# 4x4.net
KiCad netlist of a schematic drawn in EasyEDA Pro
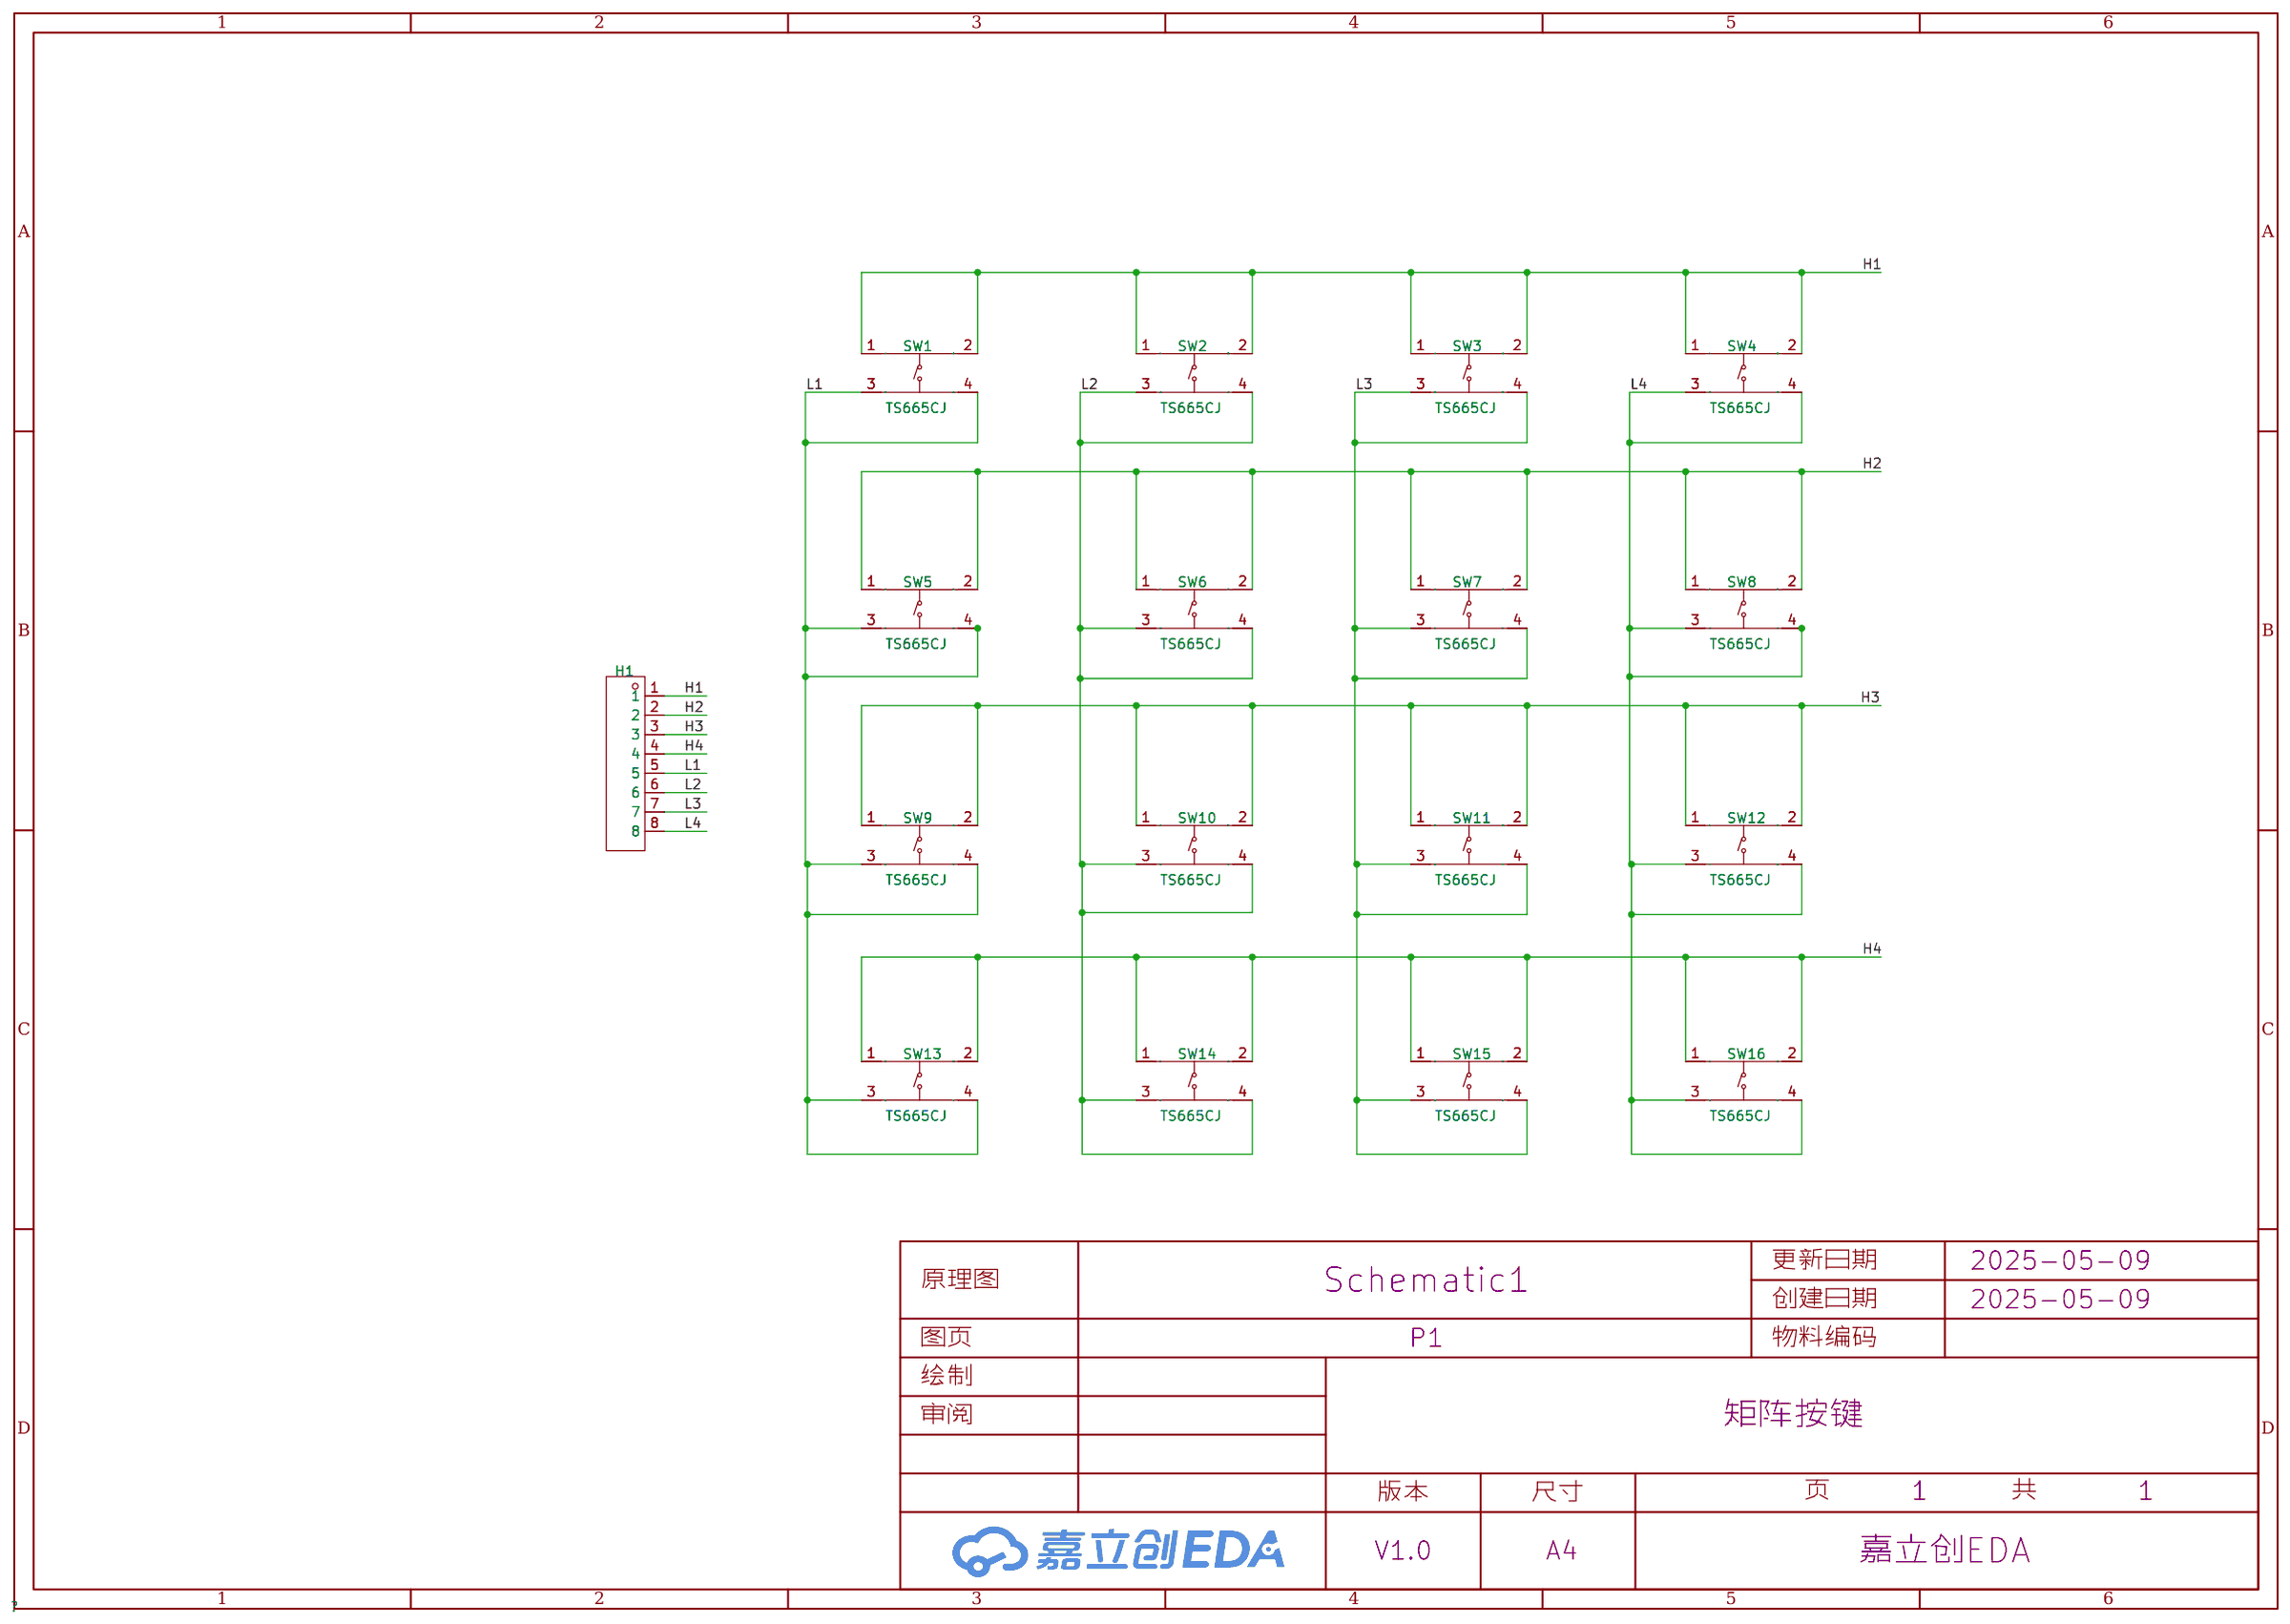
[diagram p0: schematic sheet]

(export (version "E")
  (design (tool "Eeschema 10.0.6"))
  (components
    (comp (ref "H1")
      (value "PZ254V-11-08P")
      (footprint "easyedapro:HDR-TH_8P-P2.54-V-M")
      (fields (field (name "Manufacturer") "XFCN(兴飞)"))
      (libsource (lib "easyedapro") (part "PZ254V-11-08P"))
    )
    (comp (ref "SW1")
      (value "TS665CJ")
      (footprint "easyedapro:SW-TH_4P-L6.0-W6.0-P4.50-LS6.5")
      (description "电路结构:单刀单掷;按钮形状:圆形按钮;安装方式:直插;开关长度:6mm;开关宽度:6mm;开关高度:5mm;触点电流:50mA;额定电压(DC):12V;带灯:-;机械寿命:-;")
      (fields (field (name "Manufacturer") "SHOU HAN(首韩)"))
      (libsource (lib "easyedapro") (part "TS665CJ"))
    )
    (comp (ref "SW2")
      (value "TS665CJ")
      (footprint "easyedapro:SW-TH_4P-L6.0-W6.0-P4.50-LS6.5")
      (description "电路结构:单刀单掷;按钮形状:圆形按钮;安装方式:直插;开关长度:6mm;开关宽度:6mm;开关高度:5mm;触点电流:50mA;额定电压(DC):12V;带灯:-;机械寿命:-;")
      (fields (field (name "Manufacturer") "SHOU HAN(首韩)"))
      (libsource (lib "easyedapro") (part "TS665CJ"))
    )
    (comp (ref "SW3")
      (value "TS665CJ")
      (footprint "easyedapro:SW-TH_4P-L6.0-W6.0-P4.50-LS6.5")
      (description "电路结构:单刀单掷;按钮形状:圆形按钮;安装方式:直插;开关长度:6mm;开关宽度:6mm;开关高度:5mm;触点电流:50mA;额定电压(DC):12V;带灯:-;机械寿命:-;")
      (fields (field (name "Manufacturer") "SHOU HAN(首韩)"))
      (libsource (lib "easyedapro") (part "TS665CJ"))
    )
    (comp (ref "SW4")
      (value "TS665CJ")
      (footprint "easyedapro:SW-TH_4P-L6.0-W6.0-P4.50-LS6.5")
      (description "电路结构:单刀单掷;按钮形状:圆形按钮;安装方式:直插;开关长度:6mm;开关宽度:6mm;开关高度:5mm;触点电流:50mA;额定电压(DC):12V;带灯:-;机械寿命:-;")
      (fields (field (name "Manufacturer") "SHOU HAN(首韩)"))
      (libsource (lib "easyedapro") (part "TS665CJ"))
    )
    (comp (ref "SW5")
      (value "TS665CJ")
      (footprint "easyedapro:SW-TH_4P-L6.0-W6.0-P4.50-LS6.5")
      (description "电路结构:单刀单掷;按钮形状:圆形按钮;安装方式:直插;开关长度:6mm;开关宽度:6mm;开关高度:5mm;触点电流:50mA;额定电压(DC):12V;带灯:-;机械寿命:-;")
      (fields (field (name "Manufacturer") "SHOU HAN(首韩)"))
      (libsource (lib "easyedapro") (part "TS665CJ"))
    )
    (comp (ref "SW6")
      (value "TS665CJ")
      (footprint "easyedapro:SW-TH_4P-L6.0-W6.0-P4.50-LS6.5")
      (description "电路结构:单刀单掷;按钮形状:圆形按钮;安装方式:直插;开关长度:6mm;开关宽度:6mm;开关高度:5mm;触点电流:50mA;额定电压(DC):12V;带灯:-;机械寿命:-;")
      (fields (field (name "Manufacturer") "SHOU HAN(首韩)"))
      (libsource (lib "easyedapro") (part "TS665CJ"))
    )
    (comp (ref "SW7")
      (value "TS665CJ")
      (footprint "easyedapro:SW-TH_4P-L6.0-W6.0-P4.50-LS6.5")
      (description "电路结构:单刀单掷;按钮形状:圆形按钮;安装方式:直插;开关长度:6mm;开关宽度:6mm;开关高度:5mm;触点电流:50mA;额定电压(DC):12V;带灯:-;机械寿命:-;")
      (fields (field (name "Manufacturer") "SHOU HAN(首韩)"))
      (libsource (lib "easyedapro") (part "TS665CJ"))
    )
    (comp (ref "SW8")
      (value "TS665CJ")
      (footprint "easyedapro:SW-TH_4P-L6.0-W6.0-P4.50-LS6.5")
      (description "电路结构:单刀单掷;按钮形状:圆形按钮;安装方式:直插;开关长度:6mm;开关宽度:6mm;开关高度:5mm;触点电流:50mA;额定电压(DC):12V;带灯:-;机械寿命:-;")
      (fields (field (name "Manufacturer") "SHOU HAN(首韩)"))
      (libsource (lib "easyedapro") (part "TS665CJ"))
    )
    (comp (ref "SW9")
      (value "TS665CJ")
      (footprint "easyedapro:SW-TH_4P-L6.0-W6.0-P4.50-LS6.5")
      (description "电路结构:单刀单掷;按钮形状:圆形按钮;安装方式:直插;开关长度:6mm;开关宽度:6mm;开关高度:5mm;触点电流:50mA;额定电压(DC):12V;带灯:-;机械寿命:-;")
      (fields (field (name "Manufacturer") "SHOU HAN(首韩)"))
      (libsource (lib "easyedapro") (part "TS665CJ"))
    )
    (comp (ref "SW10")
      (value "TS665CJ")
      (footprint "easyedapro:SW-TH_4P-L6.0-W6.0-P4.50-LS6.5")
      (description "电路结构:单刀单掷;按钮形状:圆形按钮;安装方式:直插;开关长度:6mm;开关宽度:6mm;开关高度:5mm;触点电流:50mA;额定电压(DC):12V;带灯:-;机械寿命:-;")
      (fields (field (name "Manufacturer") "SHOU HAN(首韩)"))
      (libsource (lib "easyedapro") (part "TS665CJ"))
    )
    (comp (ref "SW11")
      (value "TS665CJ")
      (footprint "easyedapro:SW-TH_4P-L6.0-W6.0-P4.50-LS6.5")
      (description "电路结构:单刀单掷;按钮形状:圆形按钮;安装方式:直插;开关长度:6mm;开关宽度:6mm;开关高度:5mm;触点电流:50mA;额定电压(DC):12V;带灯:-;机械寿命:-;")
      (fields (field (name "Manufacturer") "SHOU HAN(首韩)"))
      (libsource (lib "easyedapro") (part "TS665CJ"))
    )
    (comp (ref "SW12")
      (value "TS665CJ")
      (footprint "easyedapro:SW-TH_4P-L6.0-W6.0-P4.50-LS6.5")
      (description "电路结构:单刀单掷;按钮形状:圆形按钮;安装方式:直插;开关长度:6mm;开关宽度:6mm;开关高度:5mm;触点电流:50mA;额定电压(DC):12V;带灯:-;机械寿命:-;")
      (fields (field (name "Manufacturer") "SHOU HAN(首韩)"))
      (libsource (lib "easyedapro") (part "TS665CJ"))
    )
    (comp (ref "SW13")
      (value "TS665CJ")
      (footprint "easyedapro:SW-TH_4P-L6.0-W6.0-P4.50-LS6.5")
      (description "电路结构:单刀单掷;按钮形状:圆形按钮;安装方式:直插;开关长度:6mm;开关宽度:6mm;开关高度:5mm;触点电流:50mA;额定电压(DC):12V;带灯:-;机械寿命:-;")
      (fields (field (name "Manufacturer") "SHOU HAN(首韩)"))
      (libsource (lib "easyedapro") (part "TS665CJ"))
    )
    (comp (ref "SW14")
      (value "TS665CJ")
      (footprint "easyedapro:SW-TH_4P-L6.0-W6.0-P4.50-LS6.5")
      (description "电路结构:单刀单掷;按钮形状:圆形按钮;安装方式:直插;开关长度:6mm;开关宽度:6mm;开关高度:5mm;触点电流:50mA;额定电压(DC):12V;带灯:-;机械寿命:-;")
      (fields (field (name "Manufacturer") "SHOU HAN(首韩)"))
      (libsource (lib "easyedapro") (part "TS665CJ"))
    )
    (comp (ref "SW15")
      (value "TS665CJ")
      (footprint "easyedapro:SW-TH_4P-L6.0-W6.0-P4.50-LS6.5")
      (description "电路结构:单刀单掷;按钮形状:圆形按钮;安装方式:直插;开关长度:6mm;开关宽度:6mm;开关高度:5mm;触点电流:50mA;额定电压(DC):12V;带灯:-;机械寿命:-;")
      (fields (field (name "Manufacturer") "SHOU HAN(首韩)"))
      (libsource (lib "easyedapro") (part "TS665CJ"))
    )
    (comp (ref "SW16")
      (value "TS665CJ")
      (footprint "easyedapro:SW-TH_4P-L6.0-W6.0-P4.50-LS6.5")
      (description "电路结构:单刀单掷;按钮形状:圆形按钮;安装方式:直插;开关长度:6mm;开关宽度:6mm;开关高度:5mm;触点电流:50mA;额定电压(DC):12V;带灯:-;机械寿命:-;")
      (fields (field (name "Manufacturer") "SHOU HAN(首韩)"))
      (libsource (lib "easyedapro") (part "TS665CJ"))
    )
  )
  (nets
    (net (code "1") (name "/H1") (class "Default")
      (node (ref "H1") (pin "1") (pinfunction "1_1") (pintype "unspecified"))
      (node (ref "SW1") (pin "1") (pinfunction "A_1") (pintype "unspecified"))
      (node (ref "SW1") (pin "2") (pinfunction "B_2") (pintype "unspecified"))
      (node (ref "SW2") (pin "1") (pinfunction "A_1") (pintype "unspecified"))
      (node (ref "SW2") (pin "2") (pinfunction "B_2") (pintype "unspecified"))
      (node (ref "SW3") (pin "1") (pinfunction "A_1") (pintype "unspecified"))
      (node (ref "SW3") (pin "2") (pinfunction "B_2") (pintype "unspecified"))
      (node (ref "SW4") (pin "1") (pinfunction "A_1") (pintype "unspecified"))
      (node (ref "SW4") (pin "2") (pinfunction "B_2") (pintype "unspecified"))
    )
    (net (code "2") (name "/H2") (class "Default")
      (node (ref "H1") (pin "2") (pinfunction "2_2") (pintype "unspecified"))
      (node (ref "SW5") (pin "1") (pinfunction "A_1") (pintype "unspecified"))
      (node (ref "SW5") (pin "2") (pinfunction "B_2") (pintype "unspecified"))
      (node (ref "SW6") (pin "1") (pinfunction "A_1") (pintype "unspecified"))
      (node (ref "SW6") (pin "2") (pinfunction "B_2") (pintype "unspecified"))
      (node (ref "SW7") (pin "1") (pinfunction "A_1") (pintype "unspecified"))
      (node (ref "SW7") (pin "2") (pinfunction "B_2") (pintype "unspecified"))
      (node (ref "SW8") (pin "1") (pinfunction "A_1") (pintype "unspecified"))
      (node (ref "SW8") (pin "2") (pinfunction "B_2") (pintype "unspecified"))
    )
    (net (code "3") (name "/H3") (class "Default")
      (node (ref "H1") (pin "3") (pinfunction "3_3") (pintype "unspecified"))
      (node (ref "SW10") (pin "1") (pinfunction "A_1") (pintype "unspecified"))
      (node (ref "SW10") (pin "2") (pinfunction "B_2") (pintype "unspecified"))
      (node (ref "SW11") (pin "1") (pinfunction "A_1") (pintype "unspecified"))
      (node (ref "SW11") (pin "2") (pinfunction "B_2") (pintype "unspecified"))
      (node (ref "SW12") (pin "1") (pinfunction "A_1") (pintype "unspecified"))
      (node (ref "SW12") (pin "2") (pinfunction "B_2") (pintype "unspecified"))
      (node (ref "SW9") (pin "1") (pinfunction "A_1") (pintype "unspecified"))
      (node (ref "SW9") (pin "2") (pinfunction "B_2") (pintype "unspecified"))
    )
    (net (code "4") (name "/H4") (class "Default")
      (node (ref "H1") (pin "4") (pinfunction "4_4") (pintype "unspecified"))
      (node (ref "SW13") (pin "1") (pinfunction "A_1") (pintype "unspecified"))
      (node (ref "SW13") (pin "2") (pinfunction "B_2") (pintype "unspecified"))
      (node (ref "SW14") (pin "1") (pinfunction "A_1") (pintype "unspecified"))
      (node (ref "SW14") (pin "2") (pinfunction "B_2") (pintype "unspecified"))
      (node (ref "SW15") (pin "1") (pinfunction "A_1") (pintype "unspecified"))
      (node (ref "SW15") (pin "2") (pinfunction "B_2") (pintype "unspecified"))
      (node (ref "SW16") (pin "1") (pinfunction "A_1") (pintype "unspecified"))
      (node (ref "SW16") (pin "2") (pinfunction "B_2") (pintype "unspecified"))
    )
    (net (code "5") (name "/L1") (class "Default")
      (node (ref "H1") (pin "5") (pinfunction "5_5") (pintype "unspecified"))
      (node (ref "SW1") (pin "3") (pinfunction "C_3") (pintype "unspecified"))
      (node (ref "SW1") (pin "4") (pinfunction "D_4") (pintype "unspecified"))
      (node (ref "SW13") (pin "3") (pinfunction "C_3") (pintype "unspecified"))
      (node (ref "SW13") (pin "4") (pinfunction "D_4") (pintype "unspecified"))
      (node (ref "SW5") (pin "3") (pinfunction "C_3") (pintype "unspecified"))
      (node (ref "SW5") (pin "4") (pinfunction "D_4") (pintype "unspecified"))
      (node (ref "SW9") (pin "3") (pinfunction "C_3") (pintype "unspecified"))
      (node (ref "SW9") (pin "4") (pinfunction "D_4") (pintype "unspecified"))
    )
    (net (code "6") (name "/L2") (class "Default")
      (node (ref "H1") (pin "6") (pinfunction "6_6") (pintype "unspecified"))
      (node (ref "SW10") (pin "3") (pinfunction "C_3") (pintype "unspecified"))
      (node (ref "SW10") (pin "4") (pinfunction "D_4") (pintype "unspecified"))
      (node (ref "SW14") (pin "3") (pinfunction "C_3") (pintype "unspecified"))
      (node (ref "SW14") (pin "4") (pinfunction "D_4") (pintype "unspecified"))
      (node (ref "SW2") (pin "3") (pinfunction "C_3") (pintype "unspecified"))
      (node (ref "SW2") (pin "4") (pinfunction "D_4") (pintype "unspecified"))
      (node (ref "SW6") (pin "3") (pinfunction "C_3") (pintype "unspecified"))
      (node (ref "SW6") (pin "4") (pinfunction "D_4") (pintype "unspecified"))
    )
    (net (code "7") (name "/L3") (class "Default")
      (node (ref "H1") (pin "7") (pinfunction "7_7") (pintype "unspecified"))
      (node (ref "SW11") (pin "3") (pinfunction "C_3") (pintype "unspecified"))
      (node (ref "SW11") (pin "4") (pinfunction "D_4") (pintype "unspecified"))
      (node (ref "SW15") (pin "3") (pinfunction "C_3") (pintype "unspecified"))
      (node (ref "SW15") (pin "4") (pinfunction "D_4") (pintype "unspecified"))
      (node (ref "SW3") (pin "3") (pinfunction "C_3") (pintype "unspecified"))
      (node (ref "SW3") (pin "4") (pinfunction "D_4") (pintype "unspecified"))
      (node (ref "SW7") (pin "3") (pinfunction "C_3") (pintype "unspecified"))
      (node (ref "SW7") (pin "4") (pinfunction "D_4") (pintype "unspecified"))
    )
    (net (code "8") (name "/L4") (class "Default")
      (node (ref "H1") (pin "8") (pinfunction "8_8") (pintype "unspecified"))
      (node (ref "SW12") (pin "3") (pinfunction "C_3") (pintype "unspecified"))
      (node (ref "SW12") (pin "4") (pinfunction "D_4") (pintype "unspecified"))
      (node (ref "SW16") (pin "3") (pinfunction "C_3") (pintype "unspecified"))
      (node (ref "SW16") (pin "4") (pinfunction "D_4") (pintype "unspecified"))
      (node (ref "SW4") (pin "3") (pinfunction "C_3") (pintype "unspecified"))
      (node (ref "SW4") (pin "4") (pinfunction "D_4") (pintype "unspecified"))
      (node (ref "SW8") (pin "3") (pinfunction "C_3") (pintype "unspecified"))
      (node (ref "SW8") (pin "4") (pinfunction "D_4") (pintype "unspecified"))
    )
  )
)
